# 2_waffling80-ALPS_matrix.net
KiCad netlist of a schematic drawn in Altium Designer
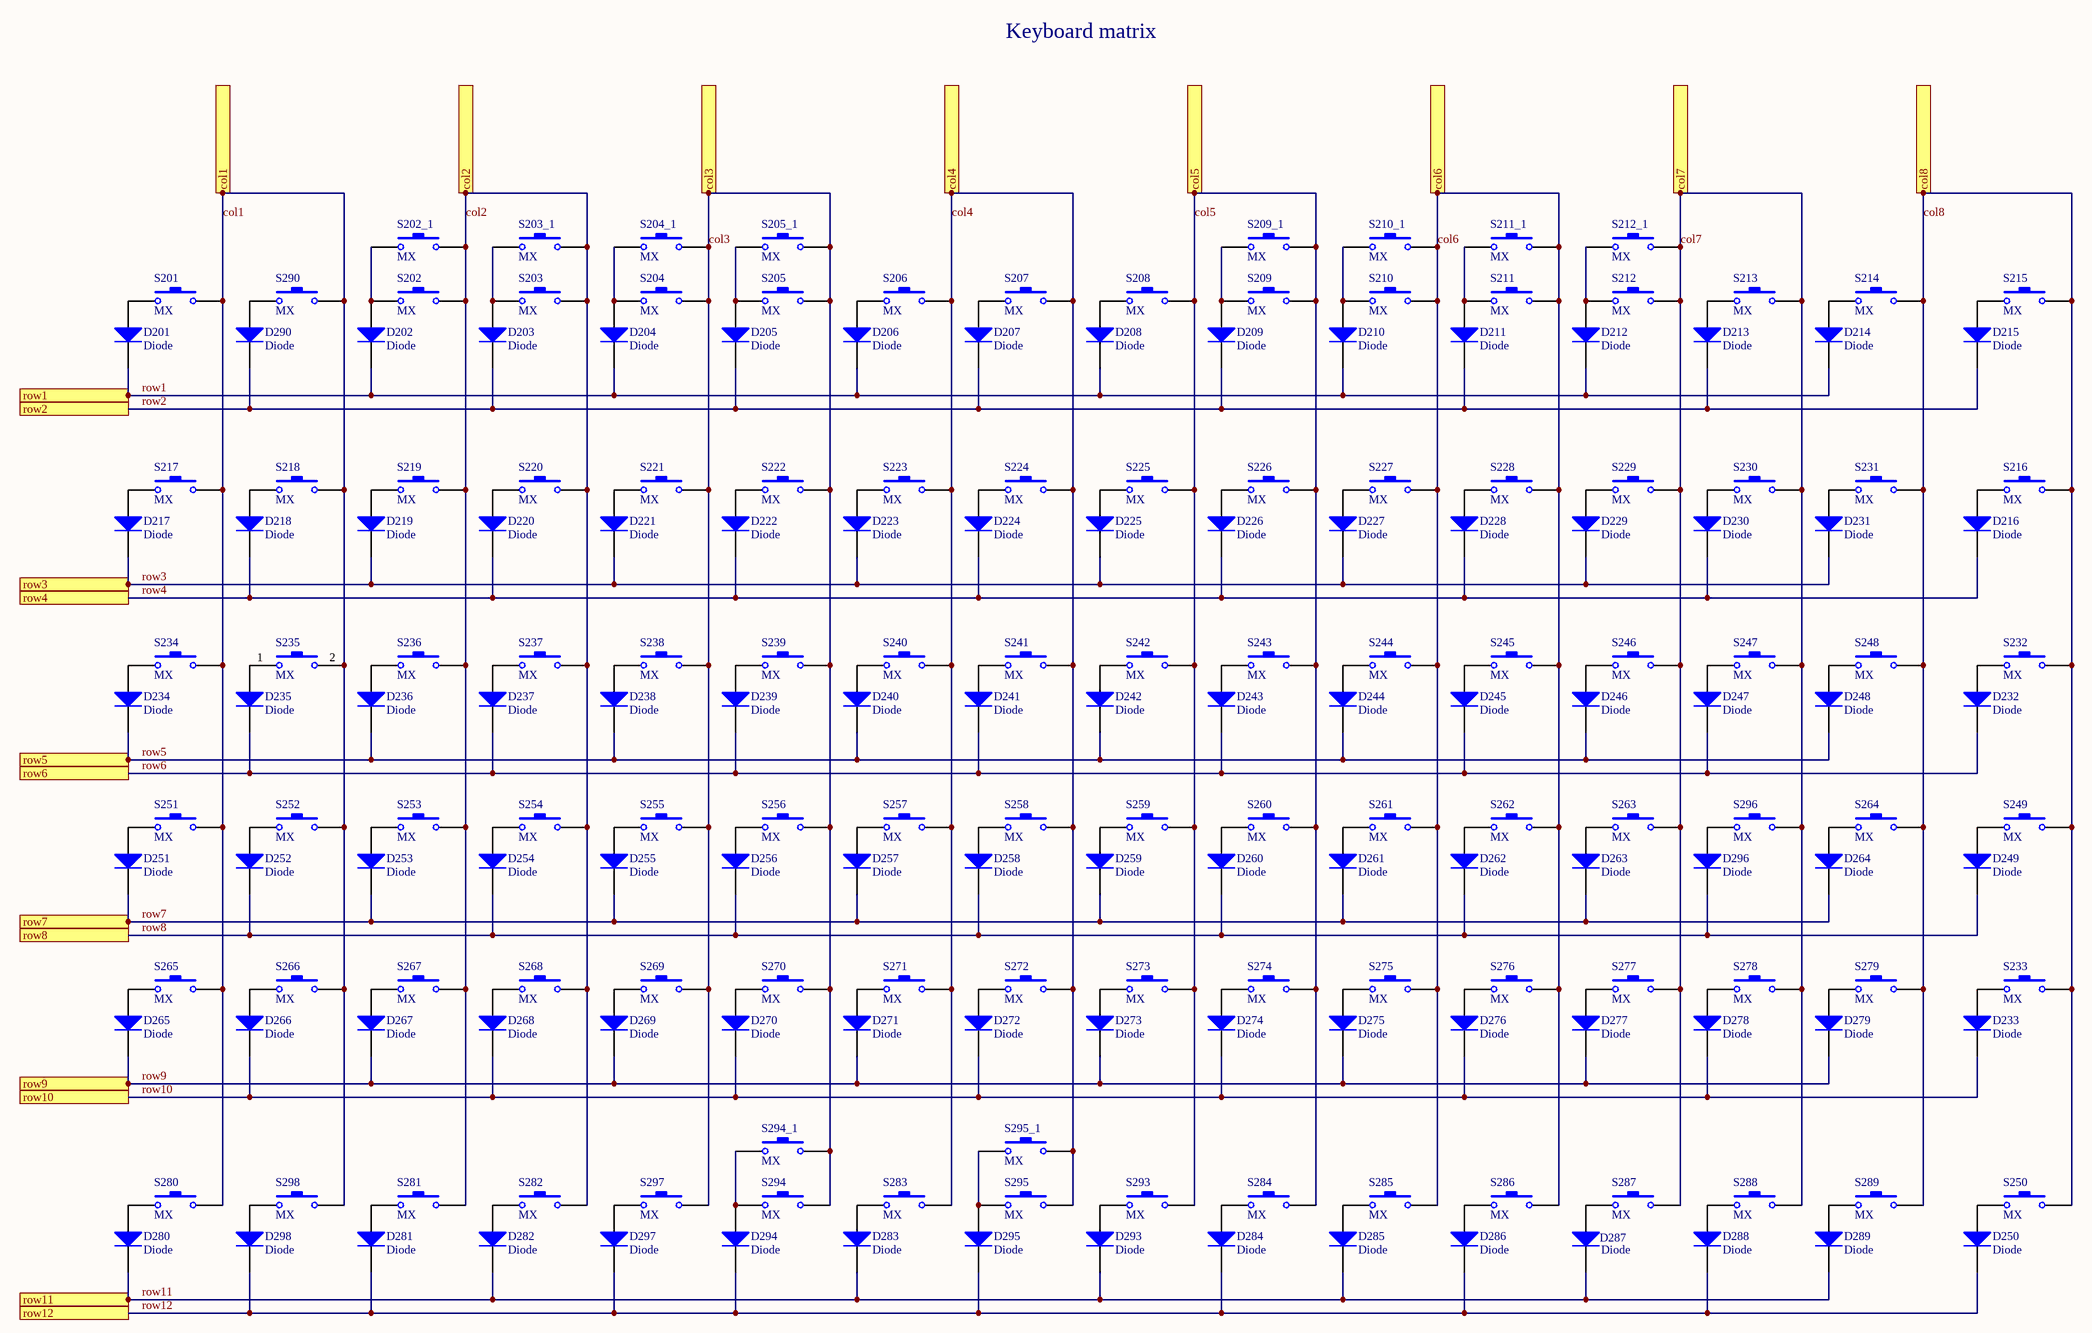
[diagram p0: 2_waffling80-ALPS_matrix.SchDoc]

(export (version "E")
  (design (tool "Eeschema 10.0.6"))
  (components
    (comp (ref "D201")
      (value "Diode")
      (footprint "SOD-123")
      (description "Default Diode")
      (fields (field (name "LCSC PART #") "C81598") (field (name "MRF.PART") "1N4148W"))
      (libsource (lib "Miscellaneous Devices") (part "Diode"))
    )
    (comp (ref "D202")
      (value "Diode")
      (footprint "SOD-123")
      (description "Default Diode")
      (fields (field (name "LCSC PART #") "C81598") (field (name "MRF.PART") "1N4148W"))
      (libsource (lib "Miscellaneous Devices") (part "Diode"))
    )
    (comp (ref "D203")
      (value "Diode")
      (footprint "SOD-123")
      (description "Default Diode")
      (fields (field (name "LCSC PART #") "C81598") (field (name "MRF.PART") "1N4148W"))
      (libsource (lib "Miscellaneous Devices") (part "Diode"))
    )
    (comp (ref "D204")
      (value "Diode")
      (footprint "SOD-123")
      (description "Default Diode")
      (fields (field (name "LCSC PART #") "C81598") (field (name "MRF.PART") "1N4148W"))
      (libsource (lib "Miscellaneous Devices") (part "Diode"))
    )
    (comp (ref "D205")
      (value "Diode")
      (footprint "SOD-123")
      (description "Default Diode")
      (fields (field (name "LCSC PART #") "C81598") (field (name "MRF.PART") "1N4148W"))
      (libsource (lib "Miscellaneous Devices") (part "Diode"))
    )
    (comp (ref "D206")
      (value "Diode")
      (footprint "SOD-123")
      (description "Default Diode")
      (fields (field (name "LCSC PART #") "C81598") (field (name "MRF.PART") "1N4148W"))
      (libsource (lib "Miscellaneous Devices") (part "Diode"))
    )
    (comp (ref "D207")
      (value "Diode")
      (footprint "SOD-123")
      (description "Default Diode")
      (fields (field (name "LCSC PART #") "C81598") (field (name "MRF.PART") "1N4148W"))
      (libsource (lib "Miscellaneous Devices") (part "Diode"))
    )
    (comp (ref "D208")
      (value "Diode")
      (footprint "SOD-123")
      (description "Default Diode")
      (fields (field (name "LCSC PART #") "C81598") (field (name "MRF.PART") "1N4148W"))
      (libsource (lib "Miscellaneous Devices") (part "Diode"))
    )
    (comp (ref "D209")
      (value "Diode")
      (footprint "SOD-123")
      (description "Default Diode")
      (fields (field (name "LCSC PART #") "C81598") (field (name "MRF.PART") "1N4148W"))
      (libsource (lib "Miscellaneous Devices") (part "Diode"))
    )
    (comp (ref "D210")
      (value "Diode")
      (footprint "SOD-123")
      (description "Default Diode")
      (fields (field (name "LCSC PART #") "C81598") (field (name "MRF.PART") "1N4148W"))
      (libsource (lib "Miscellaneous Devices") (part "Diode"))
    )
    (comp (ref "D211")
      (value "Diode")
      (footprint "SOD-123")
      (description "Default Diode")
      (fields (field (name "LCSC PART #") "C81598") (field (name "MRF.PART") "1N4148W"))
      (libsource (lib "Miscellaneous Devices") (part "Diode"))
    )
    (comp (ref "D212")
      (value "Diode")
      (footprint "SOD-123")
      (description "Default Diode")
      (fields (field (name "LCSC PART #") "C81598") (field (name "MRF.PART") "1N4148W"))
      (libsource (lib "Miscellaneous Devices") (part "Diode"))
    )
    (comp (ref "D213")
      (value "Diode")
      (footprint "SOD-123")
      (description "Default Diode")
      (fields (field (name "LCSC PART #") "C81598") (field (name "MRF.PART") "1N4148W"))
      (libsource (lib "Miscellaneous Devices") (part "Diode"))
    )
    (comp (ref "D214")
      (value "Diode")
      (footprint "SOD-123")
      (description "Default Diode")
      (fields (field (name "LCSC PART #") "C81598") (field (name "MRF.PART") "1N4148W"))
      (libsource (lib "Miscellaneous Devices") (part "Diode"))
    )
    (comp (ref "D215")
      (value "Diode")
      (footprint "SOD-123")
      (description "Default Diode")
      (fields (field (name "LCSC PART #") "C81598") (field (name "MRF.PART") "1N4148W"))
      (libsource (lib "Miscellaneous Devices") (part "Diode"))
    )
    (comp (ref "D216")
      (value "Diode")
      (footprint "SOD-123")
      (description "Default Diode")
      (fields (field (name "LCSC PART #") "C81598") (field (name "MRF.PART") "1N4148W"))
      (libsource (lib "Miscellaneous Devices") (part "Diode"))
    )
    (comp (ref "D217")
      (value "Diode")
      (footprint "SOD-123")
      (description "Default Diode")
      (fields (field (name "LCSC PART #") "C81598") (field (name "MRF.PART") "1N4148W"))
      (libsource (lib "Miscellaneous Devices") (part "Diode"))
    )
    (comp (ref "D218")
      (value "Diode")
      (footprint "SOD-123")
      (description "Default Diode")
      (fields (field (name "LCSC PART #") "C81598") (field (name "MRF.PART") "1N4148W"))
      (libsource (lib "Miscellaneous Devices") (part "Diode"))
    )
    (comp (ref "D219")
      (value "Diode")
      (footprint "SOD-123")
      (description "Default Diode")
      (fields (field (name "LCSC PART #") "C81598") (field (name "MRF.PART") "1N4148W"))
      (libsource (lib "Miscellaneous Devices") (part "Diode"))
    )
    (comp (ref "D220")
      (value "Diode")
      (footprint "SOD-123")
      (description "Default Diode")
      (fields (field (name "LCSC PART #") "C81598") (field (name "MRF.PART") "1N4148W"))
      (libsource (lib "Miscellaneous Devices") (part "Diode"))
    )
    (comp (ref "D221")
      (value "Diode")
      (footprint "SOD-123")
      (description "Default Diode")
      (fields (field (name "LCSC PART #") "C81598") (field (name "MRF.PART") "1N4148W"))
      (libsource (lib "Miscellaneous Devices") (part "Diode"))
    )
    (comp (ref "D222")
      (value "Diode")
      (footprint "SOD-123")
      (description "Default Diode")
      (fields (field (name "LCSC PART #") "C81598") (field (name "MRF.PART") "1N4148W"))
      (libsource (lib "Miscellaneous Devices") (part "Diode"))
    )
    (comp (ref "D223")
      (value "Diode")
      (footprint "SOD-123")
      (description "Default Diode")
      (fields (field (name "LCSC PART #") "C81598") (field (name "MRF.PART") "1N4148W"))
      (libsource (lib "Miscellaneous Devices") (part "Diode"))
    )
    (comp (ref "D224")
      (value "Diode")
      (footprint "SOD-123")
      (description "Default Diode")
      (fields (field (name "LCSC PART #") "C81598") (field (name "MRF.PART") "1N4148W"))
      (libsource (lib "Miscellaneous Devices") (part "Diode"))
    )
    (comp (ref "D225")
      (value "Diode")
      (footprint "SOD-123")
      (description "Default Diode")
      (fields (field (name "LCSC PART #") "C81598") (field (name "MRF.PART") "1N4148W"))
      (libsource (lib "Miscellaneous Devices") (part "Diode"))
    )
    (comp (ref "D226")
      (value "Diode")
      (footprint "SOD-123")
      (description "Default Diode")
      (fields (field (name "LCSC PART #") "C81598") (field (name "MRF.PART") "1N4148W"))
      (libsource (lib "Miscellaneous Devices") (part "Diode"))
    )
    (comp (ref "D227")
      (value "Diode")
      (footprint "SOD-123")
      (description "Default Diode")
      (fields (field (name "LCSC PART #") "C81598") (field (name "MRF.PART") "1N4148W"))
      (libsource (lib "Miscellaneous Devices") (part "Diode"))
    )
    (comp (ref "D228")
      (value "Diode")
      (footprint "SOD-123")
      (description "Default Diode")
      (fields (field (name "LCSC PART #") "C81598") (field (name "MRF.PART") "1N4148W"))
      (libsource (lib "Miscellaneous Devices") (part "Diode"))
    )
    (comp (ref "D229")
      (value "Diode")
      (footprint "SOD-123")
      (description "Default Diode")
      (fields (field (name "LCSC PART #") "C81598") (field (name "MRF.PART") "1N4148W"))
      (libsource (lib "Miscellaneous Devices") (part "Diode"))
    )
    (comp (ref "D230")
      (value "Diode")
      (footprint "SOD-123")
      (description "Default Diode")
      (fields (field (name "LCSC PART #") "C81598") (field (name "MRF.PART") "1N4148W"))
      (libsource (lib "Miscellaneous Devices") (part "Diode"))
    )
    (comp (ref "D231")
      (value "Diode")
      (footprint "SOD-123")
      (description "Default Diode")
      (fields (field (name "LCSC PART #") "C81598") (field (name "MRF.PART") "1N4148W"))
      (libsource (lib "Miscellaneous Devices") (part "Diode"))
    )
    (comp (ref "D232")
      (value "Diode")
      (footprint "SOD-123")
      (description "Default Diode")
      (fields (field (name "LCSC PART #") "C81598") (field (name "MRF.PART") "1N4148W"))
      (libsource (lib "Miscellaneous Devices") (part "Diode"))
    )
    (comp (ref "D233")
      (value "Diode")
      (footprint "SOD-123")
      (description "Default Diode")
      (fields (field (name "LCSC PART #") "C81598") (field (name "MRF.PART") "1N4148W"))
      (libsource (lib "Miscellaneous Devices") (part "Diode"))
    )
    (comp (ref "D234")
      (value "Diode")
      (footprint "SOD-123")
      (description "Default Diode")
      (fields (field (name "LCSC PART #") "C81598") (field (name "MRF.PART") "1N4148W"))
      (libsource (lib "Miscellaneous Devices") (part "Diode"))
    )
    (comp (ref "D235")
      (value "Diode")
      (footprint "SOD-123")
      (description "Default Diode")
      (fields (field (name "LCSC PART #") "C81598") (field (name "MRF.PART") "1N4148W"))
      (libsource (lib "Miscellaneous Devices") (part "Diode"))
    )
    (comp (ref "D236")
      (value "Diode")
      (footprint "SOD-123")
      (description "Default Diode")
      (fields (field (name "LCSC PART #") "C81598") (field (name "MRF.PART") "1N4148W"))
      (libsource (lib "Miscellaneous Devices") (part "Diode"))
    )
    (comp (ref "D237")
      (value "Diode")
      (footprint "SOD-123")
      (description "Default Diode")
      (fields (field (name "LCSC PART #") "C81598") (field (name "MRF.PART") "1N4148W"))
      (libsource (lib "Miscellaneous Devices") (part "Diode"))
    )
    (comp (ref "D238")
      (value "Diode")
      (footprint "SOD-123")
      (description "Default Diode")
      (fields (field (name "LCSC PART #") "C81598") (field (name "MRF.PART") "1N4148W"))
      (libsource (lib "Miscellaneous Devices") (part "Diode"))
    )
    (comp (ref "D239")
      (value "Diode")
      (footprint "SOD-123")
      (description "Default Diode")
      (fields (field (name "LCSC PART #") "C81598") (field (name "MRF.PART") "1N4148W"))
      (libsource (lib "Miscellaneous Devices") (part "Diode"))
    )
    (comp (ref "D240")
      (value "Diode")
      (footprint "SOD-123")
      (description "Default Diode")
      (fields (field (name "LCSC PART #") "C81598") (field (name "MRF.PART") "1N4148W"))
      (libsource (lib "Miscellaneous Devices") (part "Diode"))
    )
    (comp (ref "D241")
      (value "Diode")
      (footprint "SOD-123")
      (description "Default Diode")
      (fields (field (name "LCSC PART #") "C81598") (field (name "MRF.PART") "1N4148W"))
      (libsource (lib "Miscellaneous Devices") (part "Diode"))
    )
    (comp (ref "D242")
      (value "Diode")
      (footprint "SOD-123")
      (description "Default Diode")
      (fields (field (name "LCSC PART #") "C81598") (field (name "MRF.PART") "1N4148W"))
      (libsource (lib "Miscellaneous Devices") (part "Diode"))
    )
    (comp (ref "D243")
      (value "Diode")
      (footprint "SOD-123")
      (description "Default Diode")
      (fields (field (name "LCSC PART #") "C81598") (field (name "MRF.PART") "1N4148W"))
      (libsource (lib "Miscellaneous Devices") (part "Diode"))
    )
    (comp (ref "D244")
      (value "Diode")
      (footprint "SOD-123")
      (description "Default Diode")
      (fields (field (name "LCSC PART #") "C81598") (field (name "MRF.PART") "1N4148W"))
      (libsource (lib "Miscellaneous Devices") (part "Diode"))
    )
    (comp (ref "D245")
      (value "Diode")
      (footprint "SOD-123")
      (description "Default Diode")
      (fields (field (name "LCSC PART #") "C81598") (field (name "MRF.PART") "1N4148W"))
      (libsource (lib "Miscellaneous Devices") (part "Diode"))
    )
    (comp (ref "D246")
      (value "Diode")
      (footprint "SOD-123")
      (description "Default Diode")
      (fields (field (name "LCSC PART #") "C81598") (field (name "MRF.PART") "1N4148W"))
      (libsource (lib "Miscellaneous Devices") (part "Diode"))
    )
    (comp (ref "D247")
      (value "Diode")
      (footprint "SOD-123")
      (description "Default Diode")
      (fields (field (name "LCSC PART #") "C81598") (field (name "MRF.PART") "1N4148W"))
      (libsource (lib "Miscellaneous Devices") (part "Diode"))
    )
    (comp (ref "D248")
      (value "Diode")
      (footprint "SOD-123")
      (description "Default Diode")
      (fields (field (name "LCSC PART #") "C81598") (field (name "MRF.PART") "1N4148W"))
      (libsource (lib "Miscellaneous Devices") (part "Diode"))
    )
    (comp (ref "D249")
      (value "Diode")
      (footprint "SOD-123")
      (description "Default Diode")
      (fields (field (name "LCSC PART #") "C81598") (field (name "MRF.PART") "1N4148W"))
      (libsource (lib "Miscellaneous Devices") (part "Diode"))
    )
    (comp (ref "D250")
      (value "Diode")
      (footprint "SOD-123")
      (description "Default Diode")
      (fields (field (name "LCSC PART #") "C81598") (field (name "MRF.PART") "1N4148W"))
      (libsource (lib "Miscellaneous Devices") (part "Diode"))
    )
    (comp (ref "D251")
      (value "Diode")
      (footprint "SOD-123")
      (description "Default Diode")
      (fields (field (name "LCSC PART #") "C81598") (field (name "MRF.PART") "1N4148W"))
      (libsource (lib "Miscellaneous Devices") (part "Diode"))
    )
    (comp (ref "D252")
      (value "Diode")
      (footprint "SOD-123")
      (description "Default Diode")
      (fields (field (name "LCSC PART #") "C81598") (field (name "MRF.PART") "1N4148W"))
      (libsource (lib "Miscellaneous Devices") (part "Diode"))
    )
    (comp (ref "D253")
      (value "Diode")
      (footprint "SOD-123")
      (description "Default Diode")
      (fields (field (name "LCSC PART #") "C81598") (field (name "MRF.PART") "1N4148W"))
      (libsource (lib "Miscellaneous Devices") (part "Diode"))
    )
    (comp (ref "D254")
      (value "Diode")
      (footprint "SOD-123")
      (description "Default Diode")
      (fields (field (name "LCSC PART #") "C81598") (field (name "MRF.PART") "1N4148W"))
      (libsource (lib "Miscellaneous Devices") (part "Diode"))
    )
    (comp (ref "D255")
      (value "Diode")
      (footprint "SOD-123")
      (description "Default Diode")
      (fields (field (name "LCSC PART #") "C81598") (field (name "MRF.PART") "1N4148W"))
      (libsource (lib "Miscellaneous Devices") (part "Diode"))
    )
    (comp (ref "D256")
      (value "Diode")
      (footprint "SOD-123")
      (description "Default Diode")
      (fields (field (name "LCSC PART #") "C81598") (field (name "MRF.PART") "1N4148W"))
      (libsource (lib "Miscellaneous Devices") (part "Diode"))
    )
    (comp (ref "D257")
      (value "Diode")
      (footprint "SOD-123")
      (description "Default Diode")
      (fields (field (name "LCSC PART #") "C81598") (field (name "MRF.PART") "1N4148W"))
      (libsource (lib "Miscellaneous Devices") (part "Diode"))
    )
    (comp (ref "D258")
      (value "Diode")
      (footprint "SOD-123")
      (description "Default Diode")
      (fields (field (name "LCSC PART #") "C81598") (field (name "MRF.PART") "1N4148W"))
      (libsource (lib "Miscellaneous Devices") (part "Diode"))
    )
    (comp (ref "D259")
      (value "Diode")
      (footprint "SOD-123")
      (description "Default Diode")
      (fields (field (name "LCSC PART #") "C81598") (field (name "MRF.PART") "1N4148W"))
      (libsource (lib "Miscellaneous Devices") (part "Diode"))
    )
    (comp (ref "D260")
      (value "Diode")
      (footprint "SOD-123")
      (description "Default Diode")
      (fields (field (name "LCSC PART #") "C81598") (field (name "MRF.PART") "1N4148W"))
      (libsource (lib "Miscellaneous Devices") (part "Diode"))
    )
    (comp (ref "D261")
      (value "Diode")
      (footprint "SOD-123")
      (description "Default Diode")
      (fields (field (name "LCSC PART #") "C81598") (field (name "MRF.PART") "1N4148W"))
      (libsource (lib "Miscellaneous Devices") (part "Diode"))
    )
    (comp (ref "D262")
      (value "Diode")
      (footprint "SOD-123")
      (description "Default Diode")
      (fields (field (name "LCSC PART #") "C81598") (field (name "MRF.PART") "1N4148W"))
      (libsource (lib "Miscellaneous Devices") (part "Diode"))
    )
    (comp (ref "D263")
      (value "Diode")
      (footprint "SOD-123")
      (description "Default Diode")
      (fields (field (name "LCSC PART #") "C81598") (field (name "MRF.PART") "1N4148W"))
      (libsource (lib "Miscellaneous Devices") (part "Diode"))
    )
    (comp (ref "D264")
      (value "Diode")
      (footprint "SOD-123")
      (description "Default Diode")
      (fields (field (name "LCSC PART #") "C81598") (field (name "MRF.PART") "1N4148W"))
      (libsource (lib "Miscellaneous Devices") (part "Diode"))
    )
    (comp (ref "D265")
      (value "Diode")
      (footprint "SOD-123")
      (description "Default Diode")
      (fields (field (name "LCSC PART #") "C81598") (field (name "MRF.PART") "1N4148W"))
      (libsource (lib "Miscellaneous Devices") (part "Diode"))
    )
    (comp (ref "D266")
      (value "Diode")
      (footprint "SOD-123")
      (description "Default Diode")
      (fields (field (name "LCSC PART #") "C81598") (field (name "MRF.PART") "1N4148W"))
      (libsource (lib "Miscellaneous Devices") (part "Diode"))
    )
    (comp (ref "D267")
      (value "Diode")
      (footprint "SOD-123")
      (description "Default Diode")
      (fields (field (name "LCSC PART #") "C81598") (field (name "MRF.PART") "1N4148W"))
      (libsource (lib "Miscellaneous Devices") (part "Diode"))
    )
    (comp (ref "D268")
      (value "Diode")
      (footprint "SOD-123")
      (description "Default Diode")
      (fields (field (name "LCSC PART #") "C81598") (field (name "MRF.PART") "1N4148W"))
      (libsource (lib "Miscellaneous Devices") (part "Diode"))
    )
    (comp (ref "D269")
      (value "Diode")
      (footprint "SOD-123")
      (description "Default Diode")
      (fields (field (name "LCSC PART #") "C81598") (field (name "MRF.PART") "1N4148W"))
      (libsource (lib "Miscellaneous Devices") (part "Diode"))
    )
    (comp (ref "D270")
      (value "Diode")
      (footprint "SOD-123")
      (description "Default Diode")
      (fields (field (name "LCSC PART #") "C81598") (field (name "MRF.PART") "1N4148W"))
      (libsource (lib "Miscellaneous Devices") (part "Diode"))
    )
    (comp (ref "D271")
      (value "Diode")
      (footprint "SOD-123")
      (description "Default Diode")
      (fields (field (name "LCSC PART #") "C81598") (field (name "MRF.PART") "1N4148W"))
      (libsource (lib "Miscellaneous Devices") (part "Diode"))
    )
    (comp (ref "D272")
      (value "Diode")
      (footprint "SOD-123")
      (description "Default Diode")
      (fields (field (name "LCSC PART #") "C81598") (field (name "MRF.PART") "1N4148W"))
      (libsource (lib "Miscellaneous Devices") (part "Diode"))
    )
    (comp (ref "D273")
      (value "Diode")
      (footprint "SOD-123")
      (description "Default Diode")
      (fields (field (name "LCSC PART #") "C81598") (field (name "MRF.PART") "1N4148W"))
      (libsource (lib "Miscellaneous Devices") (part "Diode"))
    )
    (comp (ref "D274")
      (value "Diode")
      (footprint "SOD-123")
      (description "Default Diode")
      (fields (field (name "LCSC PART #") "C81598") (field (name "MRF.PART") "1N4148W"))
      (libsource (lib "Miscellaneous Devices") (part "Diode"))
    )
    (comp (ref "D275")
      (value "Diode")
      (footprint "SOD-123")
      (description "Default Diode")
      (fields (field (name "LCSC PART #") "C81598") (field (name "MRF.PART") "1N4148W"))
      (libsource (lib "Miscellaneous Devices") (part "Diode"))
    )
    (comp (ref "D276")
      (value "Diode")
      (footprint "SOD-123")
      (description "Default Diode")
      (fields (field (name "LCSC PART #") "C81598") (field (name "MRF.PART") "1N4148W"))
      (libsource (lib "Miscellaneous Devices") (part "Diode"))
    )
    (comp (ref "D277")
      (value "Diode")
      (footprint "SOD-123")
      (description "Default Diode")
      (fields (field (name "LCSC PART #") "C81598") (field (name "MRF.PART") "1N4148W"))
      (libsource (lib "Miscellaneous Devices") (part "Diode"))
    )
    (comp (ref "D278")
      (value "Diode")
      (footprint "SOD-123")
      (description "Default Diode")
      (fields (field (name "LCSC PART #") "C81598") (field (name "MRF.PART") "1N4148W"))
      (libsource (lib "Miscellaneous Devices") (part "Diode"))
    )
    (comp (ref "D279")
      (value "Diode")
      (footprint "SOD-123")
      (description "Default Diode")
      (fields (field (name "LCSC PART #") "C81598") (field (name "MRF.PART") "1N4148W"))
      (libsource (lib "Miscellaneous Devices") (part "Diode"))
    )
    (comp (ref "D280")
      (value "Diode")
      (footprint "SOD-123")
      (description "Default Diode")
      (fields (field (name "LCSC PART #") "C81598") (field (name "MRF.PART") "1N4148W"))
      (libsource (lib "Miscellaneous Devices") (part "Diode"))
    )
    (comp (ref "D281")
      (value "Diode")
      (footprint "SOD-123")
      (description "Default Diode")
      (fields (field (name "LCSC PART #") "C81598") (field (name "MRF.PART") "1N4148W"))
      (libsource (lib "Miscellaneous Devices") (part "Diode"))
    )
    (comp (ref "D282")
      (value "Diode")
      (footprint "SOD-123")
      (description "Default Diode")
      (fields (field (name "LCSC PART #") "C81598") (field (name "MRF.PART") "1N4148W"))
      (libsource (lib "Miscellaneous Devices") (part "Diode"))
    )
    (comp (ref "D283")
      (value "Diode")
      (footprint "SOD-123")
      (description "Default Diode")
      (fields (field (name "LCSC PART #") "C81598") (field (name "MRF.PART") "1N4148W"))
      (libsource (lib "Miscellaneous Devices") (part "Diode"))
    )
    (comp (ref "D284")
      (value "Diode")
      (footprint "SOD-123")
      (description "Default Diode")
      (fields (field (name "LCSC PART #") "C81598") (field (name "MRF.PART") "1N4148W"))
      (libsource (lib "Miscellaneous Devices") (part "Diode"))
    )
    (comp (ref "D285")
      (value "Diode")
      (footprint "SOD-123")
      (description "Default Diode")
      (fields (field (name "LCSC PART #") "C81598") (field (name "MRF.PART") "1N4148W"))
      (libsource (lib "Miscellaneous Devices") (part "Diode"))
    )
    (comp (ref "D286")
      (value "Diode")
      (footprint "SOD-123")
      (description "Default Diode")
      (fields (field (name "LCSC PART #") "C81598") (field (name "MRF.PART") "1N4148W"))
      (libsource (lib "Miscellaneous Devices") (part "Diode"))
    )
    (comp (ref "D287")
      (value "Diode")
      (footprint "SOD-123")
      (description "Default Diode")
      (fields (field (name "LCSC PART #") "C81598") (field (name "MRF.PART") "1N4148W"))
      (libsource (lib "Miscellaneous Devices") (part "Diode"))
    )
    (comp (ref "D288")
      (value "Diode")
      (footprint "SOD-123")
      (description "Default Diode")
      (fields (field (name "LCSC PART #") "C81598") (field (name "MRF.PART") "1N4148W"))
      (libsource (lib "Miscellaneous Devices") (part "Diode"))
    )
    (comp (ref "D289")
      (value "Diode")
      (footprint "SOD-123")
      (description "Default Diode")
      (fields (field (name "LCSC PART #") "C81598") (field (name "MRF.PART") "1N4148W"))
      (libsource (lib "Miscellaneous Devices") (part "Diode"))
    )
    (comp (ref "D290")
      (value "Diode")
      (footprint "SOD-123")
      (description "Default Diode")
      (fields (field (name "LCSC PART #") "C81598") (field (name "MRF.PART") "1N4148W"))
      (libsource (lib "Miscellaneous Devices") (part "Diode"))
    )
    (comp (ref "D293")
      (value "Diode")
      (footprint "SOD-123")
      (description "Default Diode")
      (fields (field (name "LCSC PART #") "C81598") (field (name "MRF.PART") "1N4148W"))
      (libsource (lib "Miscellaneous Devices") (part "Diode"))
    )
    (comp (ref "D294")
      (value "Diode")
      (footprint "SOD-123")
      (description "Default Diode")
      (fields (field (name "LCSC PART #") "C81598") (field (name "MRF.PART") "1N4148W"))
      (libsource (lib "Miscellaneous Devices") (part "Diode"))
    )
    (comp (ref "D295")
      (value "Diode")
      (footprint "SOD-123")
      (description "Default Diode")
      (fields (field (name "LCSC PART #") "C81598") (field (name "MRF.PART") "1N4148W"))
      (libsource (lib "Miscellaneous Devices") (part "Diode"))
    )
    (comp (ref "D296")
      (value "Diode")
      (footprint "SOD-123")
      (description "Default Diode")
      (fields (field (name "LCSC PART #") "C81598") (field (name "MRF.PART") "1N4148W"))
      (libsource (lib "Miscellaneous Devices") (part "Diode"))
    )
    (comp (ref "D297")
      (value "Diode")
      (footprint "SOD-123")
      (description "Default Diode")
      (fields (field (name "LCSC PART #") "C81598") (field (name "MRF.PART") "1N4148W"))
      (libsource (lib "Miscellaneous Devices") (part "Diode"))
    )
    (comp (ref "D298")
      (value "Diode")
      (footprint "SOD-123")
      (description "Default Diode")
      (fields (field (name "LCSC PART #") "C81598") (field (name "MRF.PART") "1N4148W"))
      (libsource (lib "Miscellaneous Devices") (part "Diode"))
    )
    (comp (ref "S201")
      (value "MX")
      (footprint "Alps-switch - switched pol")
      (description "Switch")
      (libsource (lib "Miscellaneous Devices") (part "SW-PB"))
    )
    (comp (ref "S202")
      (value "MX")
      (footprint "Alps-switch - switched pol")
      (description "Switch")
      (libsource (lib "Miscellaneous Devices") (part "SW-PB"))
    )
    (comp (ref "S202_1")
      (value "MX")
      (footprint "Alps-switch")
      (description "Switch")
      (libsource (lib "Miscellaneous Devices") (part "SW-PB"))
    )
    (comp (ref "S203")
      (value "MX")
      (footprint "Alps-switch - switched pol")
      (description "Switch")
      (libsource (lib "Miscellaneous Devices") (part "SW-PB"))
    )
    (comp (ref "S203_1")
      (value "MX")
      (footprint "Alps-switch")
      (description "Switch")
      (libsource (lib "Miscellaneous Devices") (part "SW-PB"))
    )
    (comp (ref "S204")
      (value "MX")
      (footprint "Alps-switch - switched pol")
      (description "Switch")
      (libsource (lib "Miscellaneous Devices") (part "SW-PB"))
    )
    (comp (ref "S204_1")
      (value "MX")
      (footprint "Alps-switch")
      (description "Switch")
      (libsource (lib "Miscellaneous Devices") (part "SW-PB"))
    )
    (comp (ref "S205")
      (value "MX")
      (footprint "Alps-switch - switched pol")
      (description "Switch")
      (libsource (lib "Miscellaneous Devices") (part "SW-PB"))
    )
    (comp (ref "S205_1")
      (value "MX")
      (footprint "Alps-switch")
      (description "Switch")
      (libsource (lib "Miscellaneous Devices") (part "SW-PB"))
    )
    (comp (ref "S206")
      (value "MX")
      (footprint "Alps-switch")
      (description "Switch")
      (libsource (lib "Miscellaneous Devices") (part "SW-PB"))
    )
    (comp (ref "S207")
      (value "MX")
      (footprint "Alps-switch")
      (description "Switch")
      (libsource (lib "Miscellaneous Devices") (part "SW-PB"))
    )
    (comp (ref "S208")
      (value "MX")
      (footprint "Alps-switch")
      (description "Switch")
      (libsource (lib "Miscellaneous Devices") (part "SW-PB"))
    )
    (comp (ref "S209")
      (value "MX")
      (footprint "Alps-switch - switched pol")
      (description "Switch")
      (libsource (lib "Miscellaneous Devices") (part "SW-PB"))
    )
    (comp (ref "S209_1")
      (value "MX")
      (footprint "Alps-switch")
      (description "Switch")
      (libsource (lib "Miscellaneous Devices") (part "SW-PB"))
    )
    (comp (ref "S210")
      (value "MX")
      (footprint "Alps-switch")
      (description "Switch")
      (libsource (lib "Miscellaneous Devices") (part "SW-PB"))
    )
    (comp (ref "S210_1")
      (value "MX")
      (footprint "Alps-switch - switched pol")
      (description "Switch")
      (libsource (lib "Miscellaneous Devices") (part "SW-PB"))
    )
    (comp (ref "S211")
      (value "MX")
      (footprint "Alps-switch")
      (description "Switch")
      (libsource (lib "Miscellaneous Devices") (part "SW-PB"))
    )
    (comp (ref "S211_1")
      (value "MX")
      (footprint "Alps-switch - switched pol")
      (description "Switch")
      (libsource (lib "Miscellaneous Devices") (part "SW-PB"))
    )
    (comp (ref "S212")
      (value "MX")
      (footprint "Alps-switch")
      (description "Switch")
      (libsource (lib "Miscellaneous Devices") (part "SW-PB"))
    )
    (comp (ref "S212_1")
      (value "MX")
      (footprint "Alps-switch - switched pol")
      (description "Switch")
      (libsource (lib "Miscellaneous Devices") (part "SW-PB"))
    )
    (comp (ref "S213")
      (value "MX")
      (footprint "Alps-switch")
      (description "Switch")
      (libsource (lib "Miscellaneous Devices") (part "SW-PB"))
    )
    (comp (ref "S214")
      (value "MX")
      (footprint "Alps-switch - switched pol")
      (description "Switch")
      (libsource (lib "Miscellaneous Devices") (part "SW-PB"))
    )
    (comp (ref "S215")
      (value "MX")
      (footprint "Alps-switch")
      (description "Switch")
      (libsource (lib "Miscellaneous Devices") (part "SW-PB"))
    )
    (comp (ref "S216")
      (value "MX")
      (footprint "Alps-switch")
      (description "Switch")
      (libsource (lib "Miscellaneous Devices") (part "SW-PB"))
    )
    (comp (ref "S217")
      (value "MX")
      (footprint "Alps-switch - switched pol")
      (description "Switch")
      (libsource (lib "Miscellaneous Devices") (part "SW-PB"))
    )
    (comp (ref "S218")
      (value "MX")
      (footprint "Alps-switch - switched pol")
      (description "Switch")
      (libsource (lib "Miscellaneous Devices") (part "SW-PB"))
    )
    (comp (ref "S219")
      (value "MX")
      (footprint "Alps-switch - switched pol")
      (description "Switch")
      (libsource (lib "Miscellaneous Devices") (part "SW-PB"))
    )
    (comp (ref "S220")
      (value "MX")
      (footprint "Alps-switch - switched pol")
      (description "Switch")
      (libsource (lib "Miscellaneous Devices") (part "SW-PB"))
    )
    (comp (ref "S221")
      (value "MX")
      (footprint "Alps-switch - switched pol")
      (description "Switch")
      (libsource (lib "Miscellaneous Devices") (part "SW-PB"))
    )
    (comp (ref "S222")
      (value "MX")
      (footprint "Alps-switch - switched pol")
      (description "Switch")
      (libsource (lib "Miscellaneous Devices") (part "SW-PB"))
    )
    (comp (ref "S223")
      (value "MX")
      (footprint "Alps-switch - switched pol")
      (description "Switch")
      (libsource (lib "Miscellaneous Devices") (part "SW-PB"))
    )
    (comp (ref "S224")
      (value "MX")
      (footprint "Alps-switch - switched pol")
      (description "Switch")
      (libsource (lib "Miscellaneous Devices") (part "SW-PB"))
    )
    (comp (ref "S225")
      (value "MX")
      (footprint "Alps-switch - switched pol")
      (description "Switch")
      (libsource (lib "Miscellaneous Devices") (part "SW-PB"))
    )
    (comp (ref "S226")
      (value "MX")
      (footprint "Alps-switch - switched pol")
      (description "Switch")
      (libsource (lib "Miscellaneous Devices") (part "SW-PB"))
    )
    (comp (ref "S227")
      (value "MX")
      (footprint "Alps-switch - switched pol")
      (description "Switch")
      (libsource (lib "Miscellaneous Devices") (part "SW-PB"))
    )
    (comp (ref "S228")
      (value "MX")
      (footprint "Alps-switch - switched pol")
      (description "Switch")
      (libsource (lib "Miscellaneous Devices") (part "SW-PB"))
    )
    (comp (ref "S229")
      (value "MX")
      (footprint "Alps-switch - switched pol")
      (description "Switch")
      (libsource (lib "Miscellaneous Devices") (part "SW-PB"))
    )
    (comp (ref "S230")
      (value "MX")
      (footprint "Alps-switch")
      (description "Switch")
      (libsource (lib "Miscellaneous Devices") (part "SW-PB"))
    )
    (comp (ref "S231")
      (value "MX")
      (footprint "Alps-switch")
      (description "Switch")
      (libsource (lib "Miscellaneous Devices") (part "SW-PB"))
    )
    (comp (ref "S232")
      (value "MX")
      (footprint "Alps-switch")
      (description "Switch")
      (libsource (lib "Miscellaneous Devices") (part "SW-PB"))
    )
    (comp (ref "S233")
      (value "MX")
      (footprint "Alps-switch")
      (description "Switch")
      (libsource (lib "Miscellaneous Devices") (part "SW-PB"))
    )
    (comp (ref "S234")
      (value "MX")
      (footprint "Alps-switch - switched pol")
      (description "TAB")
      (libsource (lib "Miscellaneous Devices") (part "SW-PB"))
    )
    (comp (ref "S235")
      (value "MX")
      (footprint "Alps-switch - switched pol")
      (description "Switch")
      (libsource (lib "") (part "SW-PB_1"))
    )
    (comp (ref "S236")
      (value "MX")
      (footprint "Alps-switch - switched pol")
      (description "Switch")
      (libsource (lib "Miscellaneous Devices") (part "SW-PB"))
    )
    (comp (ref "S237")
      (value "MX")
      (footprint "Alps-switch - switched pol")
      (description "Switch")
      (libsource (lib "Miscellaneous Devices") (part "SW-PB"))
    )
    (comp (ref "S238")
      (value "MX")
      (footprint "Alps-switch - switched pol")
      (description "Switch")
      (libsource (lib "Miscellaneous Devices") (part "SW-PB"))
    )
    (comp (ref "S239")
      (value "MX")
      (footprint "Alps-switch - switched pol")
      (description "Switch")
      (libsource (lib "Miscellaneous Devices") (part "SW-PB"))
    )
    (comp (ref "S240")
      (value "MX")
      (footprint "Alps-switch - switched pol")
      (description "Switch")
      (libsource (lib "Miscellaneous Devices") (part "SW-PB"))
    )
    (comp (ref "S241")
      (value "MX")
      (footprint "Alps-switch - switched pol")
      (description "Switch")
      (libsource (lib "Miscellaneous Devices") (part "SW-PB"))
    )
    (comp (ref "S242")
      (value "MX")
      (footprint "Alps-switch - switched pol")
      (description "Switch")
      (libsource (lib "Miscellaneous Devices") (part "SW-PB"))
    )
    (comp (ref "S243")
      (value "MX")
      (footprint "Alps-switch - switched pol")
      (description "Switch")
      (libsource (lib "Miscellaneous Devices") (part "SW-PB"))
    )
    (comp (ref "S244")
      (value "MX")
      (footprint "Alps-switch - switched pol")
      (description "Switch")
      (libsource (lib "Miscellaneous Devices") (part "SW-PB"))
    )
    (comp (ref "S245")
      (value "MX")
      (footprint "Alps-switch - switched pol")
      (description "Switch")
      (libsource (lib "Miscellaneous Devices") (part "SW-PB"))
    )
    (comp (ref "S246")
      (value "MX")
      (footprint "Alps-switch - switched pol")
      (description "Switch")
      (libsource (lib "Miscellaneous Devices") (part "SW-PB"))
    )
    (comp (ref "S247")
      (value "MX")
      (footprint "Alps-switch")
      (description "Switch")
      (libsource (lib "Miscellaneous Devices") (part "SW-PB"))
    )
    (comp (ref "S248")
      (value "MX")
      (footprint "Alps-switch")
      (description "Switch")
      (libsource (lib "Miscellaneous Devices") (part "SW-PB"))
    )
    (comp (ref "S249")
      (value "MX")
      (footprint "Alps-switch")
      (description "Switch")
      (libsource (lib "Miscellaneous Devices") (part "SW-PB"))
    )
    (comp (ref "S250")
      (value "MX")
      (footprint "Alps-switch")
      (description "Switch")
      (libsource (lib "Miscellaneous Devices") (part "SW-PB"))
    )
    (comp (ref "S251")
      (value "MX")
      (footprint "ALPS-switch - CAPS")
      (description "Switch")
      (libsource (lib "Miscellaneous Devices") (part "SW-PB"))
    )
    (comp (ref "S252")
      (value "MX")
      (footprint "Alps-switch - switched pol")
      (description "Switch")
      (libsource (lib "Miscellaneous Devices") (part "SW-PB"))
    )
    (comp (ref "S253")
      (value "MX")
      (footprint "Alps-switch - switched pol")
      (description "Switch")
      (libsource (lib "Miscellaneous Devices") (part "SW-PB"))
    )
    (comp (ref "S254")
      (value "MX")
      (footprint "Alps-switch - switched pol")
      (description "Switch")
      (libsource (lib "Miscellaneous Devices") (part "SW-PB"))
    )
    (comp (ref "S255")
      (value "MX")
      (footprint "Alps-switch - switched pol")
      (description "Switch")
      (libsource (lib "Miscellaneous Devices") (part "SW-PB"))
    )
    (comp (ref "S256")
      (value "MX")
      (footprint "Alps-switch - switched pol")
      (description "Switch")
      (libsource (lib "Miscellaneous Devices") (part "SW-PB"))
    )
    (comp (ref "S257")
      (value "MX")
      (footprint "Alps-switch - switched pol")
      (description "Switch")
      (libsource (lib "Miscellaneous Devices") (part "SW-PB"))
    )
    (comp (ref "S258")
      (value "MX")
      (footprint "Alps-switch - switched pol")
      (description "Switch")
      (libsource (lib "Miscellaneous Devices") (part "SW-PB"))
    )
    (comp (ref "S259")
      (value "MX")
      (footprint "Alps-switch - switched pol")
      (description "Switch")
      (libsource (lib "Miscellaneous Devices") (part "SW-PB"))
    )
    (comp (ref "S260")
      (value "MX")
      (footprint "Alps-switch - switched pol")
      (description "Switch")
      (libsource (lib "Miscellaneous Devices") (part "SW-PB"))
    )
    (comp (ref "S261")
      (value "MX")
      (footprint "Alps-switch")
      (description "Switch")
      (libsource (lib "Miscellaneous Devices") (part "SW-PB"))
    )
    (comp (ref "S262")
      (value "MX")
      (footprint "Alps-switch - switched pol")
      (description "Switch")
      (libsource (lib "Miscellaneous Devices") (part "SW-PB"))
    )
    (comp (ref "S263")
      (value "MX")
      (footprint "Alps-switch")
      (description "Switch")
      (libsource (lib "Miscellaneous Devices") (part "SW-PB"))
    )
    (comp (ref "S264")
      (value "MX")
      (footprint "ALPS-switch - backspace")
      (description "Switch")
      (libsource (lib "Miscellaneous Devices") (part "SW-PB"))
    )
    (comp (ref "S265")
      (value "MX")
      (footprint "ALPS-switch - Left shift v2")
      (description "Switch")
      (libsource (lib "Miscellaneous Devices") (part "SW-PB"))
    )
    (comp (ref "S266")
      (value "MX")
      (footprint "Alps-switch - switched pol")
      (description "Switch")
      (libsource (lib "Miscellaneous Devices") (part "SW-PB"))
    )
    (comp (ref "S267")
      (value "MX")
      (footprint "Alps-switch - switched pol")
      (description "Switch")
      (libsource (lib "Miscellaneous Devices") (part "SW-PB"))
    )
    (comp (ref "S268")
      (value "MX")
      (footprint "Alps-switch - switched pol")
      (description "Switch")
      (libsource (lib "Miscellaneous Devices") (part "SW-PB"))
    )
    (comp (ref "S269")
      (value "MX")
      (footprint "Alps-switch - switched pol")
      (description "Switch")
      (libsource (lib "Miscellaneous Devices") (part "SW-PB"))
    )
    (comp (ref "S270")
      (value "MX")
      (footprint "Alps-switch - switched pol")
      (description "Switch")
      (libsource (lib "Miscellaneous Devices") (part "SW-PB"))
    )
    (comp (ref "S271")
      (value "MX")
      (footprint "Alps-switch - switched pol")
      (description "Switch")
      (libsource (lib "Miscellaneous Devices") (part "SW-PB"))
    )
    (comp (ref "S272")
      (value "MX")
      (footprint "Alps-switch - switched pol")
      (description "Switch")
      (libsource (lib "Miscellaneous Devices") (part "SW-PB"))
    )
    (comp (ref "S273")
      (value "MX")
      (footprint "Alps-switch - switched pol")
      (description "Switch")
      (libsource (lib "Miscellaneous Devices") (part "SW-PB"))
    )
    (comp (ref "S274")
      (value "MX")
      (footprint "Alps-switch - switched pol")
      (description "Switch")
      (libsource (lib "Miscellaneous Devices") (part "SW-PB"))
    )
    (comp (ref "S275")
      (value "MX")
      (footprint "Alps-switch - switched pol")
      (description "Switch")
      (libsource (lib "Miscellaneous Devices") (part "SW-PB"))
    )
    (comp (ref "S276")
      (value "MX")
      (footprint "Alps-switch - switched pol")
      (description "Switch")
      (libsource (lib "Miscellaneous Devices") (part "SW-PB"))
    )
    (comp (ref "S277")
      (value "MX")
      (footprint "ALPS-switch - right shift - stabs")
      (description "Switch")
      (libsource (lib "Miscellaneous Devices") (part "SW-PB"))
    )
    (comp (ref "S278")
      (value "MX")
      (footprint "Alps-switch - switched pol")
      (description "Switch")
      (libsource (lib "Miscellaneous Devices") (part "SW-PB"))
    )
    (comp (ref "S279")
      (value "MX")
      (footprint "Alps-switch")
      (description "Switch")
      (libsource (lib "Miscellaneous Devices") (part "SW-PB"))
    )
    (comp (ref "S280")
      (value "MX")
      (footprint "ALPS-switch - 1.5u MOD-L")
      (description "Switch")
      (libsource (lib "Miscellaneous Devices") (part "SW-PB"))
    )
    (comp (ref "S281")
      (value "MX")
      (footprint "ALPS-switch - L_WIN - V3")
      (description "Switch")
      (libsource (lib "Miscellaneous Devices") (part "SW-PB"))
    )
    (comp (ref "S282")
      (value "MX")
      (footprint "ALPS-SWITCH - L_ALT - V3")
      (description "Switch")
      (libsource (lib "Miscellaneous Devices") (part "SW-PB"))
    )
    (comp (ref "S283")
      (value "MX")
      (footprint "ALPS-switch - Space_V3")
      (description "Switch")
      (libsource (lib "Miscellaneous Devices") (part "SW-PB"))
    )
    (comp (ref "S284")
      (value "MX")
      (footprint "ALPS-SWITCH - R_ALT - V3")
      (description "Switch")
      (libsource (lib "Miscellaneous Devices") (part "SW-PB"))
    )
    (comp (ref "S285")
      (value "MX")
      (footprint "ALPS-switch - R_WIN V3")
      (description "Switch")
      (libsource (lib "Miscellaneous Devices") (part "SW-PB"))
    )
    (comp (ref "S286")
      (value "MX")
      (footprint "ALPS-switch - 1.5u MOD-R")
      (description "Switch")
      (libsource (lib "Miscellaneous Devices") (part "SW-PB"))
    )
    (comp (ref "S287")
      (value "MX")
      (footprint "Alps-switch")
      (description "Switch")
      (libsource (lib "Miscellaneous Devices") (part "SW-PB"))
    )
    (comp (ref "S288")
      (value "MX")
      (footprint "Alps-switch")
      (description "Switch")
      (libsource (lib "Miscellaneous Devices") (part "SW-PB"))
    )
    (comp (ref "S289")
      (value "MX")
      (footprint "Alps-switch")
      (description "Switch")
      (libsource (lib "Miscellaneous Devices") (part "SW-PB"))
    )
    (comp (ref "S290")
      (value "MX")
      (footprint "Alps-switch")
      (description "Switch")
      (libsource (lib "Miscellaneous Devices") (part "SW-PB"))
    )
    (comp (ref "S293")
      (value "MX")
      (footprint "Alps-switch")
      (description "Switch")
      (libsource (lib "Miscellaneous Devices") (part "SW-PB"))
    )
    (comp (ref "S294")
      (value "MX")
      (footprint "ALPS-switch - 3U - rotated stab")
      (description "Switch")
      (libsource (lib "Miscellaneous Devices") (part "SW-PB"))
    )
    (comp (ref "S294_1")
      (value "MX")
      (footprint "ALPS-switch - 2.25U - rotated stab")
      (description "Switch")
      (libsource (lib "Miscellaneous Devices") (part "SW-PB"))
    )
    (comp (ref "S295")
      (value "MX")
      (footprint "ALPS-switch - 3U - rotated stab")
      (description "Switch")
      (libsource (lib "Miscellaneous Devices") (part "SW-PB"))
    )
    (comp (ref "S295_1")
      (value "MX")
      (footprint "ALPS-switch - 2.75U - Rotated stab")
      (description "Switch")
      (libsource (lib "Miscellaneous Devices") (part "SW-PB"))
    )
    (comp (ref "S296")
      (value "MX")
      (footprint "ALPS-switch - Enter")
      (description "Switch")
      (libsource (lib "Miscellaneous Devices") (part "SW-PB"))
    )
    (comp (ref "S297")
      (value "MX")
      (footprint "Alps-switch")
      (description "Switch")
      (libsource (lib "Miscellaneous Devices") (part "SW-PB"))
    )
    (comp (ref "S298")
      (value "MX")
      (footprint "Alps-switch")
      (description "Switch")
      (libsource (lib "Miscellaneous Devices") (part "SW-PB"))
    )
  )
  (nets
    (net (code "1") (name "/col1") (class "Default")
      (node (ref "S201") (pin "2") (pinfunction "2_2") (pintype "passive"))
      (node (ref "S217") (pin "2") (pinfunction "2_2") (pintype "passive"))
      (node (ref "S218") (pin "2") (pinfunction "2_2") (pintype "passive"))
      (node (ref "S234") (pin "2") (pinfunction "2_2") (pintype "passive"))
      (node (ref "S235") (pin "2") (pinfunction "2_2") (pintype "passive"))
      (node (ref "S251") (pin "2") (pinfunction "2_2") (pintype "passive"))
      (node (ref "S252") (pin "2") (pinfunction "2_2") (pintype "passive"))
      (node (ref "S265") (pin "2") (pinfunction "2_2") (pintype "passive"))
      (node (ref "S266") (pin "2") (pinfunction "2_2") (pintype "passive"))
      (node (ref "S280") (pin "1") (pinfunction "1_1") (pintype "passive"))
      (node (ref "S290") (pin "2") (pinfunction "2_2") (pintype "passive"))
      (node (ref "S298") (pin "2") (pinfunction "2_2") (pintype "passive"))
    )
    (net (code "2") (name "/col2") (class "Default")
      (node (ref "S202") (pin "2") (pinfunction "2_2") (pintype "passive"))
      (node (ref "S202_1") (pin "2") (pinfunction "2_2") (pintype "passive"))
      (node (ref "S203") (pin "2") (pinfunction "2_2") (pintype "passive"))
      (node (ref "S203_1") (pin "2") (pinfunction "2_2") (pintype "passive"))
      (node (ref "S219") (pin "2") (pinfunction "2_2") (pintype "passive"))
      (node (ref "S220") (pin "2") (pinfunction "2_2") (pintype "passive"))
      (node (ref "S236") (pin "2") (pinfunction "2_2") (pintype "passive"))
      (node (ref "S237") (pin "2") (pinfunction "2_2") (pintype "passive"))
      (node (ref "S253") (pin "2") (pinfunction "2_2") (pintype "passive"))
      (node (ref "S254") (pin "2") (pinfunction "2_2") (pintype "passive"))
      (node (ref "S267") (pin "2") (pinfunction "2_2") (pintype "passive"))
      (node (ref "S268") (pin "2") (pinfunction "2_2") (pintype "passive"))
      (node (ref "S281") (pin "1") (pinfunction "1_1") (pintype "passive"))
      (node (ref "S282") (pin "1") (pinfunction "1_1") (pintype "passive"))
    )
    (net (code "3") (name "/col3") (class "Default")
      (node (ref "S204") (pin "2") (pinfunction "2_2") (pintype "passive"))
      (node (ref "S204_1") (pin "2") (pinfunction "2_2") (pintype "passive"))
      (node (ref "S205") (pin "2") (pinfunction "2_2") (pintype "passive"))
      (node (ref "S205_1") (pin "2") (pinfunction "2_2") (pintype "passive"))
      (node (ref "S221") (pin "2") (pinfunction "2_2") (pintype "passive"))
      (node (ref "S222") (pin "2") (pinfunction "2_2") (pintype "passive"))
      (node (ref "S238") (pin "2") (pinfunction "2_2") (pintype "passive"))
      (node (ref "S239") (pin "2") (pinfunction "2_2") (pintype "passive"))
      (node (ref "S255") (pin "2") (pinfunction "2_2") (pintype "passive"))
      (node (ref "S256") (pin "2") (pinfunction "2_2") (pintype "passive"))
      (node (ref "S269") (pin "2") (pinfunction "2_2") (pintype "passive"))
      (node (ref "S270") (pin "2") (pinfunction "2_2") (pintype "passive"))
      (node (ref "S294") (pin "1") (pinfunction "1_1") (pintype "passive"))
      (node (ref "S294_1") (pin "2") (pinfunction "2_2") (pintype "passive"))
      (node (ref "S297") (pin "2") (pinfunction "2_2") (pintype "passive"))
    )
    (net (code "4") (name "/col4") (class "Default")
      (node (ref "S206") (pin "2") (pinfunction "2_2") (pintype "passive"))
      (node (ref "S207") (pin "2") (pinfunction "2_2") (pintype "passive"))
      (node (ref "S223") (pin "2") (pinfunction "2_2") (pintype "passive"))
      (node (ref "S224") (pin "2") (pinfunction "2_2") (pintype "passive"))
      (node (ref "S240") (pin "2") (pinfunction "2_2") (pintype "passive"))
      (node (ref "S241") (pin "2") (pinfunction "2_2") (pintype "passive"))
      (node (ref "S257") (pin "2") (pinfunction "2_2") (pintype "passive"))
      (node (ref "S258") (pin "2") (pinfunction "2_2") (pintype "passive"))
      (node (ref "S271") (pin "2") (pinfunction "2_2") (pintype "passive"))
      (node (ref "S272") (pin "2") (pinfunction "2_2") (pintype "passive"))
      (node (ref "S283") (pin "2") (pinfunction "2_2") (pintype "passive"))
      (node (ref "S295") (pin "1") (pinfunction "1_1") (pintype "passive"))
      (node (ref "S295_1") (pin "2") (pinfunction "2_2") (pintype "passive"))
    )
    (net (code "5") (name "/col5") (class "Default")
      (node (ref "S208") (pin "2") (pinfunction "2_2") (pintype "passive"))
      (node (ref "S209") (pin "2") (pinfunction "2_2") (pintype "passive"))
      (node (ref "S209_1") (pin "2") (pinfunction "2_2") (pintype "passive"))
      (node (ref "S225") (pin "2") (pinfunction "2_2") (pintype "passive"))
      (node (ref "S226") (pin "2") (pinfunction "2_2") (pintype "passive"))
      (node (ref "S242") (pin "2") (pinfunction "2_2") (pintype "passive"))
      (node (ref "S243") (pin "2") (pinfunction "2_2") (pintype "passive"))
      (node (ref "S259") (pin "2") (pinfunction "2_2") (pintype "passive"))
      (node (ref "S260") (pin "2") (pinfunction "2_2") (pintype "passive"))
      (node (ref "S273") (pin "2") (pinfunction "2_2") (pintype "passive"))
      (node (ref "S274") (pin "2") (pinfunction "2_2") (pintype "passive"))
      (node (ref "S284") (pin "2") (pinfunction "2_2") (pintype "passive"))
      (node (ref "S293") (pin "2") (pinfunction "2_2") (pintype "passive"))
    )
    (net (code "6") (name "/col6") (class "Default")
      (node (ref "S210") (pin "2") (pinfunction "2_2") (pintype "passive"))
      (node (ref "S210_1") (pin "2") (pinfunction "2_2") (pintype "passive"))
      (node (ref "S211") (pin "2") (pinfunction "2_2") (pintype "passive"))
      (node (ref "S211_1") (pin "2") (pinfunction "2_2") (pintype "passive"))
      (node (ref "S227") (pin "2") (pinfunction "2_2") (pintype "passive"))
      (node (ref "S228") (pin "2") (pinfunction "2_2") (pintype "passive"))
      (node (ref "S244") (pin "2") (pinfunction "2_2") (pintype "passive"))
      (node (ref "S245") (pin "2") (pinfunction "2_2") (pintype "passive"))
      (node (ref "S261") (pin "2") (pinfunction "2_2") (pintype "passive"))
      (node (ref "S262") (pin "2") (pinfunction "2_2") (pintype "passive"))
      (node (ref "S275") (pin "2") (pinfunction "2_2") (pintype "passive"))
      (node (ref "S276") (pin "2") (pinfunction "2_2") (pintype "passive"))
      (node (ref "S285") (pin "2") (pinfunction "2_2") (pintype "passive"))
      (node (ref "S286") (pin "2") (pinfunction "2_2") (pintype "passive"))
    )
    (net (code "7") (name "/col7") (class "Default")
      (node (ref "S212") (pin "2") (pinfunction "2_2") (pintype "passive"))
      (node (ref "S212_1") (pin "2") (pinfunction "2_2") (pintype "passive"))
      (node (ref "S213") (pin "2") (pinfunction "2_2") (pintype "passive"))
      (node (ref "S229") (pin "2") (pinfunction "2_2") (pintype "passive"))
      (node (ref "S230") (pin "2") (pinfunction "2_2") (pintype "passive"))
      (node (ref "S246") (pin "2") (pinfunction "2_2") (pintype "passive"))
      (node (ref "S247") (pin "2") (pinfunction "2_2") (pintype "passive"))
      (node (ref "S263") (pin "2") (pinfunction "2_2") (pintype "passive"))
      (node (ref "S277") (pin "1") (pinfunction "1_1") (pintype "passive"))
      (node (ref "S278") (pin "2") (pinfunction "2_2") (pintype "passive"))
      (node (ref "S287") (pin "2") (pinfunction "2_2") (pintype "passive"))
      (node (ref "S288") (pin "2") (pinfunction "2_2") (pintype "passive"))
      (node (ref "S296") (pin "1") (pinfunction "1_1") (pintype "passive"))
    )
    (net (code "8") (name "/col8") (class "Default")
      (node (ref "S214") (pin "2") (pinfunction "2_2") (pintype "passive"))
      (node (ref "S215") (pin "2") (pinfunction "2_2") (pintype "passive"))
      (node (ref "S216") (pin "2") (pinfunction "2_2") (pintype "passive"))
      (node (ref "S231") (pin "2") (pinfunction "2_2") (pintype "passive"))
      (node (ref "S232") (pin "2") (pinfunction "2_2") (pintype "passive"))
      (node (ref "S233") (pin "2") (pinfunction "2_2") (pintype "passive"))
      (node (ref "S248") (pin "2") (pinfunction "2_2") (pintype "passive"))
      (node (ref "S249") (pin "2") (pinfunction "2_2") (pintype "passive"))
      (node (ref "S250") (pin "2") (pinfunction "2_2") (pintype "passive"))
      (node (ref "S264") (pin "1") (pinfunction "1_1") (pintype "passive"))
      (node (ref "S279") (pin "2") (pinfunction "2_2") (pintype "passive"))
      (node (ref "S289") (pin "2") (pinfunction "2_2") (pintype "passive"))
    )
    (net (code "9") (name "/row1") (class "Default")
      (node (ref "D201") (pin "2") (pinfunction "K_2") (pintype "passive"))
      (node (ref "D202") (pin "2") (pinfunction "K_2") (pintype "passive"))
      (node (ref "D204") (pin "2") (pinfunction "K_2") (pintype "passive"))
      (node (ref "D206") (pin "2") (pinfunction "K_2") (pintype "passive"))
      (node (ref "D208") (pin "2") (pinfunction "K_2") (pintype "passive"))
      (node (ref "D210") (pin "2") (pinfunction "K_2") (pintype "passive"))
      (node (ref "D212") (pin "2") (pinfunction "K_2") (pintype "passive"))
      (node (ref "D214") (pin "2") (pinfunction "K_2") (pintype "passive"))
    )
    (net (code "10") (name "/row2") (class "Default")
      (node (ref "D203") (pin "2") (pinfunction "K_2") (pintype "passive"))
      (node (ref "D205") (pin "2") (pinfunction "K_2") (pintype "passive"))
      (node (ref "D207") (pin "2") (pinfunction "K_2") (pintype "passive"))
      (node (ref "D209") (pin "2") (pinfunction "K_2") (pintype "passive"))
      (node (ref "D211") (pin "2") (pinfunction "K_2") (pintype "passive"))
      (node (ref "D213") (pin "2") (pinfunction "K_2") (pintype "passive"))
      (node (ref "D215") (pin "2") (pinfunction "K_2") (pintype "passive"))
      (node (ref "D290") (pin "2") (pinfunction "K_2") (pintype "passive"))
    )
    (net (code "11") (name "/row3") (class "Default")
      (node (ref "D217") (pin "2") (pinfunction "K_2") (pintype "passive"))
      (node (ref "D219") (pin "2") (pinfunction "K_2") (pintype "passive"))
      (node (ref "D221") (pin "2") (pinfunction "K_2") (pintype "passive"))
      (node (ref "D223") (pin "2") (pinfunction "K_2") (pintype "passive"))
      (node (ref "D225") (pin "2") (pinfunction "K_2") (pintype "passive"))
      (node (ref "D227") (pin "2") (pinfunction "K_2") (pintype "passive"))
      (node (ref "D229") (pin "2") (pinfunction "K_2") (pintype "passive"))
      (node (ref "D231") (pin "2") (pinfunction "K_2") (pintype "passive"))
    )
    (net (code "12") (name "/row4") (class "Default")
      (node (ref "D216") (pin "2") (pinfunction "K_2") (pintype "passive"))
      (node (ref "D218") (pin "2") (pinfunction "K_2") (pintype "passive"))
      (node (ref "D220") (pin "2") (pinfunction "K_2") (pintype "passive"))
      (node (ref "D222") (pin "2") (pinfunction "K_2") (pintype "passive"))
      (node (ref "D224") (pin "2") (pinfunction "K_2") (pintype "passive"))
      (node (ref "D226") (pin "2") (pinfunction "K_2") (pintype "passive"))
      (node (ref "D228") (pin "2") (pinfunction "K_2") (pintype "passive"))
      (node (ref "D230") (pin "2") (pinfunction "K_2") (pintype "passive"))
    )
    (net (code "13") (name "/row5") (class "Default")
      (node (ref "D234") (pin "2") (pinfunction "K_2") (pintype "passive"))
      (node (ref "D236") (pin "2") (pinfunction "K_2") (pintype "passive"))
      (node (ref "D238") (pin "2") (pinfunction "K_2") (pintype "passive"))
      (node (ref "D240") (pin "2") (pinfunction "K_2") (pintype "passive"))
      (node (ref "D242") (pin "2") (pinfunction "K_2") (pintype "passive"))
      (node (ref "D244") (pin "2") (pinfunction "K_2") (pintype "passive"))
      (node (ref "D246") (pin "2") (pinfunction "K_2") (pintype "passive"))
      (node (ref "D248") (pin "2") (pinfunction "K_2") (pintype "passive"))
    )
    (net (code "14") (name "/row6") (class "Default")
      (node (ref "D232") (pin "2") (pinfunction "K_2") (pintype "passive"))
      (node (ref "D235") (pin "2") (pinfunction "K_2") (pintype "passive"))
      (node (ref "D237") (pin "2") (pinfunction "K_2") (pintype "passive"))
      (node (ref "D239") (pin "2") (pinfunction "K_2") (pintype "passive"))
      (node (ref "D241") (pin "2") (pinfunction "K_2") (pintype "passive"))
      (node (ref "D243") (pin "2") (pinfunction "K_2") (pintype "passive"))
      (node (ref "D245") (pin "2") (pinfunction "K_2") (pintype "passive"))
      (node (ref "D247") (pin "2") (pinfunction "K_2") (pintype "passive"))
    )
    (net (code "15") (name "/row7") (class "Default")
      (node (ref "D251") (pin "2") (pinfunction "K_2") (pintype "passive"))
      (node (ref "D253") (pin "2") (pinfunction "K_2") (pintype "passive"))
      (node (ref "D255") (pin "2") (pinfunction "K_2") (pintype "passive"))
      (node (ref "D257") (pin "2") (pinfunction "K_2") (pintype "passive"))
      (node (ref "D259") (pin "2") (pinfunction "K_2") (pintype "passive"))
      (node (ref "D261") (pin "2") (pinfunction "K_2") (pintype "passive"))
      (node (ref "D263") (pin "2") (pinfunction "K_2") (pintype "passive"))
      (node (ref "D264") (pin "2") (pinfunction "K_2") (pintype "passive"))
    )
    (net (code "16") (name "/row8") (class "Default")
      (node (ref "D249") (pin "2") (pinfunction "K_2") (pintype "passive"))
      (node (ref "D252") (pin "2") (pinfunction "K_2") (pintype "passive"))
      (node (ref "D254") (pin "2") (pinfunction "K_2") (pintype "passive"))
      (node (ref "D256") (pin "2") (pinfunction "K_2") (pintype "passive"))
      (node (ref "D258") (pin "2") (pinfunction "K_2") (pintype "passive"))
      (node (ref "D260") (pin "2") (pinfunction "K_2") (pintype "passive"))
      (node (ref "D262") (pin "2") (pinfunction "K_2") (pintype "passive"))
      (node (ref "D296") (pin "2") (pinfunction "K_2") (pintype "passive"))
    )
    (net (code "17") (name "/row9") (class "Default")
      (node (ref "D265") (pin "2") (pinfunction "K_2") (pintype "passive"))
      (node (ref "D267") (pin "2") (pinfunction "K_2") (pintype "passive"))
      (node (ref "D269") (pin "2") (pinfunction "K_2") (pintype "passive"))
      (node (ref "D271") (pin "2") (pinfunction "K_2") (pintype "passive"))
      (node (ref "D273") (pin "2") (pinfunction "K_2") (pintype "passive"))
      (node (ref "D275") (pin "2") (pinfunction "K_2") (pintype "passive"))
      (node (ref "D277") (pin "2") (pinfunction "K_2") (pintype "passive"))
      (node (ref "D279") (pin "2") (pinfunction "K_2") (pintype "passive"))
    )
    (net (code "18") (name "/row10") (class "Default")
      (node (ref "D233") (pin "2") (pinfunction "K_2") (pintype "passive"))
      (node (ref "D266") (pin "2") (pinfunction "K_2") (pintype "passive"))
      (node (ref "D268") (pin "2") (pinfunction "K_2") (pintype "passive"))
      (node (ref "D270") (pin "2") (pinfunction "K_2") (pintype "passive"))
      (node (ref "D272") (pin "2") (pinfunction "K_2") (pintype "passive"))
      (node (ref "D274") (pin "2") (pinfunction "K_2") (pintype "passive"))
      (node (ref "D276") (pin "2") (pinfunction "K_2") (pintype "passive"))
      (node (ref "D278") (pin "2") (pinfunction "K_2") (pintype "passive"))
    )
    (net (code "19") (name "/row11") (class "Default")
      (node (ref "D280") (pin "2") (pinfunction "K_2") (pintype "passive"))
      (node (ref "D282") (pin "2") (pinfunction "K_2") (pintype "passive"))
      (node (ref "D283") (pin "2") (pinfunction "K_2") (pintype "passive"))
      (node (ref "D285") (pin "2") (pinfunction "K_2") (pintype "passive"))
      (node (ref "D287") (pin "2") (pinfunction "K_2") (pintype "passive"))
      (node (ref "D289") (pin "2") (pinfunction "K_2") (pintype "passive"))
      (node (ref "D293") (pin "2") (pinfunction "K_2") (pintype "passive"))
    )
    (net (code "20") (name "/row12") (class "Default")
      (node (ref "D250") (pin "2") (pinfunction "K_2") (pintype "passive"))
      (node (ref "D281") (pin "2") (pinfunction "K_2") (pintype "passive"))
      (node (ref "D284") (pin "2") (pinfunction "K_2") (pintype "passive"))
      (node (ref "D286") (pin "2") (pinfunction "K_2") (pintype "passive"))
      (node (ref "D288") (pin "2") (pinfunction "K_2") (pintype "passive"))
      (node (ref "D294") (pin "2") (pinfunction "K_2") (pintype "passive"))
      (node (ref "D295") (pin "2") (pinfunction "K_2") (pintype "passive"))
      (node (ref "D297") (pin "2") (pinfunction "K_2") (pintype "passive"))
      (node (ref "D298") (pin "2") (pinfunction "K_2") (pintype "passive"))
    )
    (net (code "21") (name "Net-(D201-A)") (class "Default")
      (node (ref "D201") (pin "1") (pinfunction "A_1") (pintype "passive"))
      (node (ref "S201") (pin "1") (pinfunction "1_1") (pintype "passive"))
    )
    (net (code "22") (name "Net-(D202-A)") (class "Default")
      (node (ref "D202") (pin "1") (pinfunction "A_1") (pintype "passive"))
      (node (ref "S202") (pin "1") (pinfunction "1_1") (pintype "passive"))
      (node (ref "S202_1") (pin "1") (pinfunction "1_1") (pintype "passive"))
    )
    (net (code "23") (name "Net-(D203-A)") (class "Default")
      (node (ref "D203") (pin "1") (pinfunction "A_1") (pintype "passive"))
      (node (ref "S203") (pin "1") (pinfunction "1_1") (pintype "passive"))
      (node (ref "S203_1") (pin "1") (pinfunction "1_1") (pintype "passive"))
    )
    (net (code "24") (name "Net-(D204-A)") (class "Default")
      (node (ref "D204") (pin "1") (pinfunction "A_1") (pintype "passive"))
      (node (ref "S204") (pin "1") (pinfunction "1_1") (pintype "passive"))
      (node (ref "S204_1") (pin "1") (pinfunction "1_1") (pintype "passive"))
    )
    (net (code "25") (name "Net-(D205-A)") (class "Default")
      (node (ref "D205") (pin "1") (pinfunction "A_1") (pintype "passive"))
      (node (ref "S205") (pin "1") (pinfunction "1_1") (pintype "passive"))
      (node (ref "S205_1") (pin "1") (pinfunction "1_1") (pintype "passive"))
    )
    (net (code "26") (name "Net-(D206-A)") (class "Default")
      (node (ref "D206") (pin "1") (pinfunction "A_1") (pintype "passive"))
      (node (ref "S206") (pin "1") (pinfunction "1_1") (pintype "passive"))
    )
    (net (code "27") (name "Net-(D207-A)") (class "Default")
      (node (ref "D207") (pin "1") (pinfunction "A_1") (pintype "passive"))
      (node (ref "S207") (pin "1") (pinfunction "1_1") (pintype "passive"))
    )
    (net (code "28") (name "Net-(D208-A)") (class "Default")
      (node (ref "D208") (pin "1") (pinfunction "A_1") (pintype "passive"))
      (node (ref "S208") (pin "1") (pinfunction "1_1") (pintype "passive"))
    )
    (net (code "29") (name "Net-(D209-A)") (class "Default")
      (node (ref "D209") (pin "1") (pinfunction "A_1") (pintype "passive"))
      (node (ref "S209") (pin "1") (pinfunction "1_1") (pintype "passive"))
      (node (ref "S209_1") (pin "1") (pinfunction "1_1") (pintype "passive"))
    )
    (net (code "30") (name "Net-(D210-A)") (class "Default")
      (node (ref "D210") (pin "1") (pinfunction "A_1") (pintype "passive"))
      (node (ref "S210") (pin "1") (pinfunction "1_1") (pintype "passive"))
      (node (ref "S210_1") (pin "1") (pinfunction "1_1") (pintype "passive"))
    )
    (net (code "31") (name "Net-(D211-A)") (class "Default")
      (node (ref "D211") (pin "1") (pinfunction "A_1") (pintype "passive"))
      (node (ref "S211") (pin "1") (pinfunction "1_1") (pintype "passive"))
      (node (ref "S211_1") (pin "1") (pinfunction "1_1") (pintype "passive"))
    )
    (net (code "32") (name "Net-(D212-A)") (class "Default")
      (node (ref "D212") (pin "1") (pinfunction "A_1") (pintype "passive"))
      (node (ref "S212") (pin "1") (pinfunction "1_1") (pintype "passive"))
      (node (ref "S212_1") (pin "1") (pinfunction "1_1") (pintype "passive"))
    )
    (net (code "33") (name "Net-(D213-A)") (class "Default")
      (node (ref "D213") (pin "1") (pinfunction "A_1") (pintype "passive"))
      (node (ref "S213") (pin "1") (pinfunction "1_1") (pintype "passive"))
    )
    (net (code "34") (name "Net-(D214-A)") (class "Default")
      (node (ref "D214") (pin "1") (pinfunction "A_1") (pintype "passive"))
      (node (ref "S214") (pin "1") (pinfunction "1_1") (pintype "passive"))
    )
    (net (code "35") (name "Net-(D215-A)") (class "Default")
      (node (ref "D215") (pin "1") (pinfunction "A_1") (pintype "passive"))
      (node (ref "S215") (pin "1") (pinfunction "1_1") (pintype "passive"))
    )
    (net (code "36") (name "Net-(D216-A)") (class "Default")
      (node (ref "D216") (pin "1") (pinfunction "A_1") (pintype "passive"))
      (node (ref "S216") (pin "1") (pinfunction "1_1") (pintype "passive"))
    )
    (net (code "37") (name "Net-(D217-A)") (class "Default")
      (node (ref "D217") (pin "1") (pinfunction "A_1") (pintype "passive"))
      (node (ref "S217") (pin "1") (pinfunction "1_1") (pintype "passive"))
    )
    (net (code "38") (name "Net-(D218-A)") (class "Default")
      (node (ref "D218") (pin "1") (pinfunction "A_1") (pintype "passive"))
      (node (ref "S218") (pin "1") (pinfunction "1_1") (pintype "passive"))
    )
    (net (code "39") (name "Net-(D219-A)") (class "Default")
      (node (ref "D219") (pin "1") (pinfunction "A_1") (pintype "passive"))
      (node (ref "S219") (pin "1") (pinfunction "1_1") (pintype "passive"))
    )
    (net (code "40") (name "Net-(D220-A)") (class "Default")
      (node (ref "D220") (pin "1") (pinfunction "A_1") (pintype "passive"))
      (node (ref "S220") (pin "1") (pinfunction "1_1") (pintype "passive"))
    )
    (net (code "41") (name "Net-(D221-A)") (class "Default")
      (node (ref "D221") (pin "1") (pinfunction "A_1") (pintype "passive"))
      (node (ref "S221") (pin "1") (pinfunction "1_1") (pintype "passive"))
    )
    (net (code "42") (name "Net-(D222-A)") (class "Default")
      (node (ref "D222") (pin "1") (pinfunction "A_1") (pintype "passive"))
      (node (ref "S222") (pin "1") (pinfunction "1_1") (pintype "passive"))
    )
    (net (code "43") (name "Net-(D223-A)") (class "Default")
      (node (ref "D223") (pin "1") (pinfunction "A_1") (pintype "passive"))
      (node (ref "S223") (pin "1") (pinfunction "1_1") (pintype "passive"))
    )
    (net (code "44") (name "Net-(D224-A)") (class "Default")
      (node (ref "D224") (pin "1") (pinfunction "A_1") (pintype "passive"))
      (node (ref "S224") (pin "1") (pinfunction "1_1") (pintype "passive"))
    )
    (net (code "45") (name "Net-(D225-A)") (class "Default")
      (node (ref "D225") (pin "1") (pinfunction "A_1") (pintype "passive"))
      (node (ref "S225") (pin "1") (pinfunction "1_1") (pintype "passive"))
    )
    (net (code "46") (name "Net-(D226-A)") (class "Default")
      (node (ref "D226") (pin "1") (pinfunction "A_1") (pintype "passive"))
      (node (ref "S226") (pin "1") (pinfunction "1_1") (pintype "passive"))
    )
    (net (code "47") (name "Net-(D227-A)") (class "Default")
      (node (ref "D227") (pin "1") (pinfunction "A_1") (pintype "passive"))
      (node (ref "S227") (pin "1") (pinfunction "1_1") (pintype "passive"))
    )
    (net (code "48") (name "Net-(D228-A)") (class "Default")
      (node (ref "D228") (pin "1") (pinfunction "A_1") (pintype "passive"))
      (node (ref "S228") (pin "1") (pinfunction "1_1") (pintype "passive"))
    )
    (net (code "49") (name "Net-(D229-A)") (class "Default")
      (node (ref "D229") (pin "1") (pinfunction "A_1") (pintype "passive"))
      (node (ref "S229") (pin "1") (pinfunction "1_1") (pintype "passive"))
    )
    (net (code "50") (name "Net-(D230-A)") (class "Default")
      (node (ref "D230") (pin "1") (pinfunction "A_1") (pintype "passive"))
      (node (ref "S230") (pin "1") (pinfunction "1_1") (pintype "passive"))
    )
    (net (code "51") (name "Net-(D231-A)") (class "Default")
      (node (ref "D231") (pin "1") (pinfunction "A_1") (pintype "passive"))
      (node (ref "S231") (pin "1") (pinfunction "1_1") (pintype "passive"))
    )
    (net (code "52") (name "Net-(D232-A)") (class "Default")
      (node (ref "D232") (pin "1") (pinfunction "A_1") (pintype "passive"))
      (node (ref "S232") (pin "1") (pinfunction "1_1") (pintype "passive"))
    )
    (net (code "53") (name "Net-(D233-A)") (class "Default")
      (node (ref "D233") (pin "1") (pinfunction "A_1") (pintype "passive"))
      (node (ref "S233") (pin "1") (pinfunction "1_1") (pintype "passive"))
    )
    (net (code "54") (name "Net-(D234-A)") (class "Default")
      (node (ref "D234") (pin "1") (pinfunction "A_1") (pintype "passive"))
      (node (ref "S234") (pin "1") (pinfunction "1_1") (pintype "passive"))
    )
    (net (code "55") (name "Net-(D235-A)") (class "Default")
      (node (ref "D235") (pin "1") (pinfunction "A_1") (pintype "passive"))
      (node (ref "S235") (pin "1") (pinfunction "1_1") (pintype "passive"))
    )
    (net (code "56") (name "Net-(D236-A)") (class "Default")
      (node (ref "D236") (pin "1") (pinfunction "A_1") (pintype "passive"))
      (node (ref "S236") (pin "1") (pinfunction "1_1") (pintype "passive"))
    )
    (net (code "57") (name "Net-(D237-A)") (class "Default")
      (node (ref "D237") (pin "1") (pinfunction "A_1") (pintype "passive"))
      (node (ref "S237") (pin "1") (pinfunction "1_1") (pintype "passive"))
    )
    (net (code "58") (name "Net-(D238-A)") (class "Default")
      (node (ref "D238") (pin "1") (pinfunction "A_1") (pintype "passive"))
      (node (ref "S238") (pin "1") (pinfunction "1_1") (pintype "passive"))
    )
    (net (code "59") (name "Net-(D239-A)") (class "Default")
      (node (ref "D239") (pin "1") (pinfunction "A_1") (pintype "passive"))
      (node (ref "S239") (pin "1") (pinfunction "1_1") (pintype "passive"))
    )
    (net (code "60") (name "Net-(D240-A)") (class "Default")
      (node (ref "D240") (pin "1") (pinfunction "A_1") (pintype "passive"))
      (node (ref "S240") (pin "1") (pinfunction "1_1") (pintype "passive"))
    )
    (net (code "61") (name "Net-(D241-A)") (class "Default")
      (node (ref "D241") (pin "1") (pinfunction "A_1") (pintype "passive"))
      (node (ref "S241") (pin "1") (pinfunction "1_1") (pintype "passive"))
    )
    (net (code "62") (name "Net-(D242-A)") (class "Default")
      (node (ref "D242") (pin "1") (pinfunction "A_1") (pintype "passive"))
      (node (ref "S242") (pin "1") (pinfunction "1_1") (pintype "passive"))
    )
    (net (code "63") (name "Net-(D243-A)") (class "Default")
      (node (ref "D243") (pin "1") (pinfunction "A_1") (pintype "passive"))
      (node (ref "S243") (pin "1") (pinfunction "1_1") (pintype "passive"))
    )
    (net (code "64") (name "Net-(D244-A)") (class "Default")
      (node (ref "D244") (pin "1") (pinfunction "A_1") (pintype "passive"))
      (node (ref "S244") (pin "1") (pinfunction "1_1") (pintype "passive"))
    )
    (net (code "65") (name "Net-(D245-A)") (class "Default")
      (node (ref "D245") (pin "1") (pinfunction "A_1") (pintype "passive"))
      (node (ref "S245") (pin "1") (pinfunction "1_1") (pintype "passive"))
    )
    (net (code "66") (name "Net-(D246-A)") (class "Default")
      (node (ref "D246") (pin "1") (pinfunction "A_1") (pintype "passive"))
      (node (ref "S246") (pin "1") (pinfunction "1_1") (pintype "passive"))
    )
    (net (code "67") (name "Net-(D247-A)") (class "Default")
      (node (ref "D247") (pin "1") (pinfunction "A_1") (pintype "passive"))
      (node (ref "S247") (pin "1") (pinfunction "1_1") (pintype "passive"))
    )
    (net (code "68") (name "Net-(D248-A)") (class "Default")
      (node (ref "D248") (pin "1") (pinfunction "A_1") (pintype "passive"))
      (node (ref "S248") (pin "1") (pinfunction "1_1") (pintype "passive"))
    )
    (net (code "69") (name "Net-(D249-A)") (class "Default")
      (node (ref "D249") (pin "1") (pinfunction "A_1") (pintype "passive"))
      (node (ref "S249") (pin "1") (pinfunction "1_1") (pintype "passive"))
    )
    (net (code "70") (name "Net-(D250-A)") (class "Default")
      (node (ref "D250") (pin "1") (pinfunction "A_1") (pintype "passive"))
      (node (ref "S250") (pin "1") (pinfunction "1_1") (pintype "passive"))
    )
    (net (code "71") (name "Net-(D251-A)") (class "Default")
      (node (ref "D251") (pin "1") (pinfunction "A_1") (pintype "passive"))
      (node (ref "S251") (pin "1") (pinfunction "1_1") (pintype "passive"))
    )
    (net (code "72") (name "Net-(D252-A)") (class "Default")
      (node (ref "D252") (pin "1") (pinfunction "A_1") (pintype "passive"))
      (node (ref "S252") (pin "1") (pinfunction "1_1") (pintype "passive"))
    )
    (net (code "73") (name "Net-(D253-A)") (class "Default")
      (node (ref "D253") (pin "1") (pinfunction "A_1") (pintype "passive"))
      (node (ref "S253") (pin "1") (pinfunction "1_1") (pintype "passive"))
    )
    (net (code "74") (name "Net-(D254-A)") (class "Default")
      (node (ref "D254") (pin "1") (pinfunction "A_1") (pintype "passive"))
      (node (ref "S254") (pin "1") (pinfunction "1_1") (pintype "passive"))
    )
    (net (code "75") (name "Net-(D255-A)") (class "Default")
      (node (ref "D255") (pin "1") (pinfunction "A_1") (pintype "passive"))
      (node (ref "S255") (pin "1") (pinfunction "1_1") (pintype "passive"))
    )
    (net (code "76") (name "Net-(D256-A)") (class "Default")
      (node (ref "D256") (pin "1") (pinfunction "A_1") (pintype "passive"))
      (node (ref "S256") (pin "1") (pinfunction "1_1") (pintype "passive"))
    )
    (net (code "77") (name "Net-(D257-A)") (class "Default")
      (node (ref "D257") (pin "1") (pinfunction "A_1") (pintype "passive"))
      (node (ref "S257") (pin "1") (pinfunction "1_1") (pintype "passive"))
    )
    (net (code "78") (name "Net-(D258-A)") (class "Default")
      (node (ref "D258") (pin "1") (pinfunction "A_1") (pintype "passive"))
      (node (ref "S258") (pin "1") (pinfunction "1_1") (pintype "passive"))
    )
    (net (code "79") (name "Net-(D259-A)") (class "Default")
      (node (ref "D259") (pin "1") (pinfunction "A_1") (pintype "passive"))
      (node (ref "S259") (pin "1") (pinfunction "1_1") (pintype "passive"))
    )
    (net (code "80") (name "Net-(D260-A)") (class "Default")
      (node (ref "D260") (pin "1") (pinfunction "A_1") (pintype "passive"))
      (node (ref "S260") (pin "1") (pinfunction "1_1") (pintype "passive"))
    )
    (net (code "81") (name "Net-(D261-A)") (class "Default")
      (node (ref "D261") (pin "1") (pinfunction "A_1") (pintype "passive"))
      (node (ref "S261") (pin "1") (pinfunction "1_1") (pintype "passive"))
    )
    (net (code "82") (name "Net-(D262-A)") (class "Default")
      (node (ref "D262") (pin "1") (pinfunction "A_1") (pintype "passive"))
      (node (ref "S262") (pin "1") (pinfunction "1_1") (pintype "passive"))
    )
    (net (code "83") (name "Net-(D263-A)") (class "Default")
      (node (ref "D263") (pin "1") (pinfunction "A_1") (pintype "passive"))
      (node (ref "S263") (pin "1") (pinfunction "1_1") (pintype "passive"))
    )
    (net (code "84") (name "Net-(D264-A)") (class "Default")
      (node (ref "D264") (pin "1") (pinfunction "A_1") (pintype "passive"))
      (node (ref "S264") (pin "2") (pinfunction "2_2") (pintype "passive"))
    )
    (net (code "85") (name "Net-(D265-A)") (class "Default")
      (node (ref "D265") (pin "1") (pinfunction "A_1") (pintype "passive"))
      (node (ref "S265") (pin "1") (pinfunction "1_1") (pintype "passive"))
    )
    (net (code "86") (name "Net-(D266-A)") (class "Default")
      (node (ref "D266") (pin "1") (pinfunction "A_1") (pintype "passive"))
      (node (ref "S266") (pin "1") (pinfunction "1_1") (pintype "passive"))
    )
    (net (code "87") (name "Net-(D267-A)") (class "Default")
      (node (ref "D267") (pin "1") (pinfunction "A_1") (pintype "passive"))
      (node (ref "S267") (pin "1") (pinfunction "1_1") (pintype "passive"))
    )
    (net (code "88") (name "Net-(D268-A)") (class "Default")
      (node (ref "D268") (pin "1") (pinfunction "A_1") (pintype "passive"))
      (node (ref "S268") (pin "1") (pinfunction "1_1") (pintype "passive"))
    )
    (net (code "89") (name "Net-(D269-A)") (class "Default")
      (node (ref "D269") (pin "1") (pinfunction "A_1") (pintype "passive"))
      (node (ref "S269") (pin "1") (pinfunction "1_1") (pintype "passive"))
    )
    (net (code "90") (name "Net-(D270-A)") (class "Default")
      (node (ref "D270") (pin "1") (pinfunction "A_1") (pintype "passive"))
      (node (ref "S270") (pin "1") (pinfunction "1_1") (pintype "passive"))
    )
    (net (code "91") (name "Net-(D271-A)") (class "Default")
      (node (ref "D271") (pin "1") (pinfunction "A_1") (pintype "passive"))
      (node (ref "S271") (pin "1") (pinfunction "1_1") (pintype "passive"))
    )
    (net (code "92") (name "Net-(D272-A)") (class "Default")
      (node (ref "D272") (pin "1") (pinfunction "A_1") (pintype "passive"))
      (node (ref "S272") (pin "1") (pinfunction "1_1") (pintype "passive"))
    )
    (net (code "93") (name "Net-(D273-A)") (class "Default")
      (node (ref "D273") (pin "1") (pinfunction "A_1") (pintype "passive"))
      (node (ref "S273") (pin "1") (pinfunction "1_1") (pintype "passive"))
    )
    (net (code "94") (name "Net-(D274-A)") (class "Default")
      (node (ref "D274") (pin "1") (pinfunction "A_1") (pintype "passive"))
      (node (ref "S274") (pin "1") (pinfunction "1_1") (pintype "passive"))
    )
    (net (code "95") (name "Net-(D275-A)") (class "Default")
      (node (ref "D275") (pin "1") (pinfunction "A_1") (pintype "passive"))
      (node (ref "S275") (pin "1") (pinfunction "1_1") (pintype "passive"))
    )
    (net (code "96") (name "Net-(D276-A)") (class "Default")
      (node (ref "D276") (pin "1") (pinfunction "A_1") (pintype "passive"))
      (node (ref "S276") (pin "1") (pinfunction "1_1") (pintype "passive"))
    )
    (net (code "97") (name "Net-(D277-A)") (class "Default")
      (node (ref "D277") (pin "1") (pinfunction "A_1") (pintype "passive"))
      (node (ref "S277") (pin "2") (pinfunction "2_2") (pintype "passive"))
    )
    (net (code "98") (name "Net-(D278-A)") (class "Default")
      (node (ref "D278") (pin "1") (pinfunction "A_1") (pintype "passive"))
      (node (ref "S278") (pin "1") (pinfunction "1_1") (pintype "passive"))
    )
    (net (code "99") (name "Net-(D279-A)") (class "Default")
      (node (ref "D279") (pin "1") (pinfunction "A_1") (pintype "passive"))
      (node (ref "S279") (pin "1") (pinfunction "1_1") (pintype "passive"))
    )
    (net (code "100") (name "Net-(D280-A)") (class "Default")
      (node (ref "D280") (pin "1") (pinfunction "A_1") (pintype "passive"))
      (node (ref "S280") (pin "2") (pinfunction "2_2") (pintype "passive"))
    )
    (net (code "101") (name "Net-(D281-A)") (class "Default")
      (node (ref "D281") (pin "1") (pinfunction "A_1") (pintype "passive"))
      (node (ref "S281") (pin "2") (pinfunction "2_2") (pintype "passive"))
    )
    (net (code "102") (name "Net-(D282-A)") (class "Default")
      (node (ref "D282") (pin "1") (pinfunction "A_1") (pintype "passive"))
      (node (ref "S282") (pin "2") (pinfunction "2_2") (pintype "passive"))
    )
    (net (code "103") (name "Net-(D283-A)") (class "Default")
      (node (ref "D283") (pin "1") (pinfunction "A_1") (pintype "passive"))
      (node (ref "S283") (pin "1") (pinfunction "1_1") (pintype "passive"))
    )
    (net (code "104") (name "Net-(D284-A)") (class "Default")
      (node (ref "D284") (pin "1") (pinfunction "A_1") (pintype "passive"))
      (node (ref "S284") (pin "1") (pinfunction "1_1") (pintype "passive"))
    )
    (net (code "105") (name "Net-(D285-A)") (class "Default")
      (node (ref "D285") (pin "1") (pinfunction "A_1") (pintype "passive"))
      (node (ref "S285") (pin "1") (pinfunction "1_1") (pintype "passive"))
    )
    (net (code "106") (name "Net-(D286-A)") (class "Default")
      (node (ref "D286") (pin "1") (pinfunction "A_1") (pintype "passive"))
      (node (ref "S286") (pin "1") (pinfunction "1_1") (pintype "passive"))
    )
    (net (code "107") (name "Net-(D287-A)") (class "Default")
      (node (ref "D287") (pin "1") (pinfunction "A_1") (pintype "passive"))
      (node (ref "S287") (pin "1") (pinfunction "1_1") (pintype "passive"))
    )
    (net (code "108") (name "Net-(D288-A)") (class "Default")
      (node (ref "D288") (pin "1") (pinfunction "A_1") (pintype "passive"))
      (node (ref "S288") (pin "1") (pinfunction "1_1") (pintype "passive"))
    )
    (net (code "109") (name "Net-(D289-A)") (class "Default")
      (node (ref "D289") (pin "1") (pinfunction "A_1") (pintype "passive"))
      (node (ref "S289") (pin "1") (pinfunction "1_1") (pintype "passive"))
    )
    (net (code "110") (name "Net-(D290-A)") (class "Default")
      (node (ref "D290") (pin "1") (pinfunction "A_1") (pintype "passive"))
      (node (ref "S290") (pin "1") (pinfunction "1_1") (pintype "passive"))
    )
    (net (code "111") (name "Net-(D293-A)") (class "Default")
      (node (ref "D293") (pin "1") (pinfunction "A_1") (pintype "passive"))
      (node (ref "S293") (pin "1") (pinfunction "1_1") (pintype "passive"))
    )
    (net (code "112") (name "Net-(D294-A)") (class "Default")
      (node (ref "D294") (pin "1") (pinfunction "A_1") (pintype "passive"))
      (node (ref "S294") (pin "2") (pinfunction "2_2") (pintype "passive"))
      (node (ref "S294_1") (pin "1") (pinfunction "1_1") (pintype "passive"))
    )
    (net (code "113") (name "Net-(D295-A)") (class "Default")
      (node (ref "D295") (pin "1") (pinfunction "A_1") (pintype "passive"))
      (node (ref "S295") (pin "2") (pinfunction "2_2") (pintype "passive"))
      (node (ref "S295_1") (pin "1") (pinfunction "1_1") (pintype "passive"))
    )
    (net (code "114") (name "Net-(D296-A)") (class "Default")
      (node (ref "D296") (pin "1") (pinfunction "A_1") (pintype "passive"))
      (node (ref "S296") (pin "2") (pinfunction "2_2") (pintype "passive"))
    )
    (net (code "115") (name "Net-(D297-A)") (class "Default")
      (node (ref "D297") (pin "1") (pinfunction "A_1") (pintype "passive"))
      (node (ref "S297") (pin "1") (pinfunction "1_1") (pintype "passive"))
    )
    (net (code "116") (name "Net-(D298-A)") (class "Default")
      (node (ref "D298") (pin "1") (pinfunction "A_1") (pintype "passive"))
      (node (ref "S298") (pin "1") (pinfunction "1_1") (pintype "passive"))
    )
  )
)
